# aquaMain.net
KiCad netlist of a schematic drawn in EAGLE
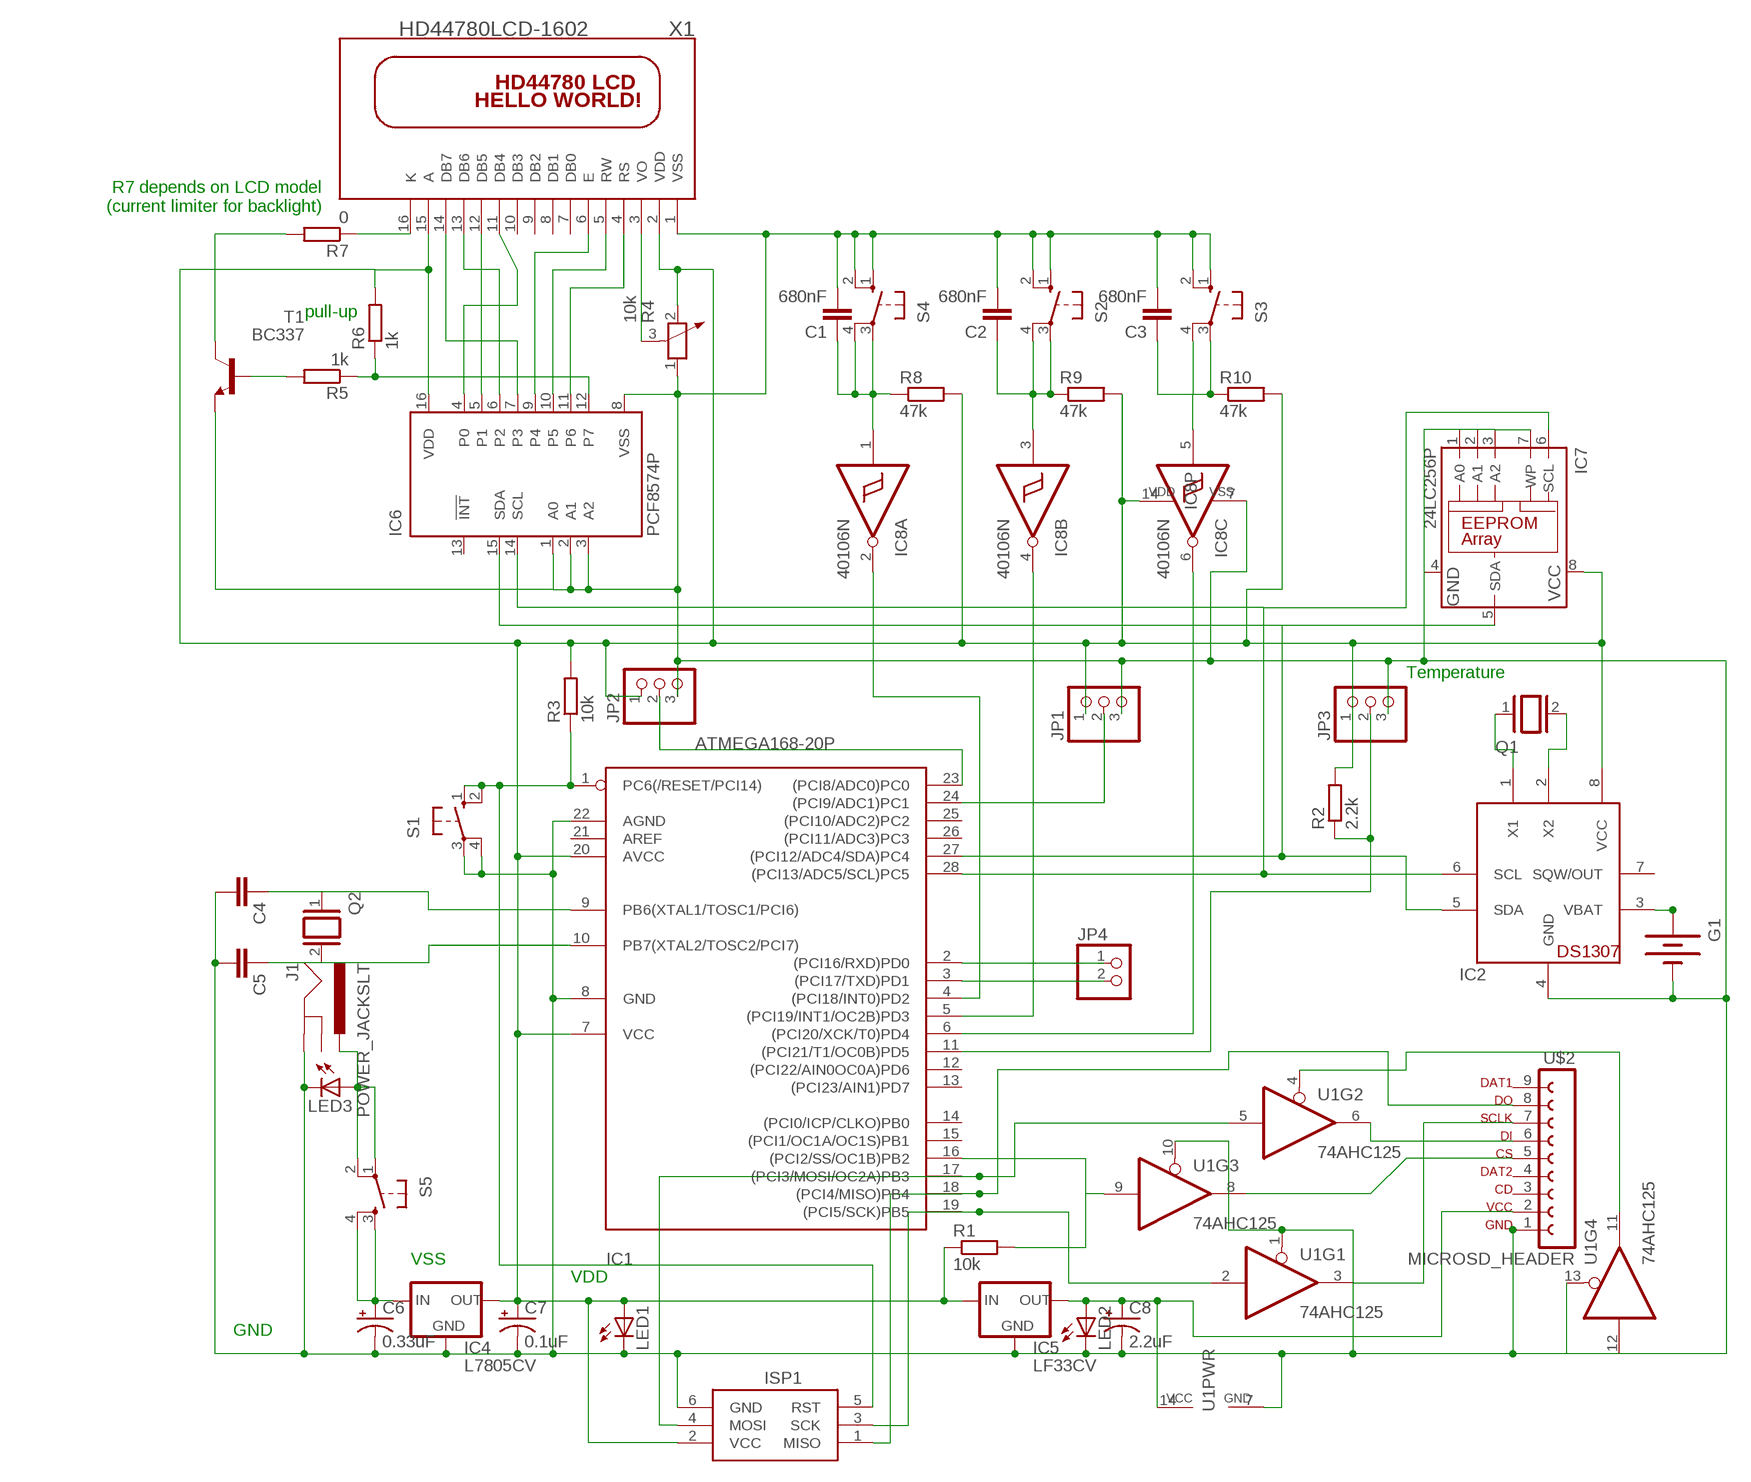
[diagram p0: schematic, sheet 1]

(export (version "E")
  (design (tool "Eeschema 10.0.6"))
  (components
    (comp (ref "C1")
      (value "680nF")
      (footprint "eagle-import:C050-050X075")
      (libsource (lib "eagle-import") (part "C-EU050-050X075"))
    )
    (comp (ref "C2")
      (value "680nF")
      (footprint "eagle-import:C050-050X075")
      (libsource (lib "eagle-import") (part "C-EU050-050X075"))
    )
    (comp (ref "C3")
      (value "680nF")
      (footprint "eagle-import:C050-050X075")
      (libsource (lib "eagle-import") (part "C-EU050-050X075"))
    )
    (comp (ref "C4")
      (value "C-EU025-024X044")
      (footprint "eagle-import:C025-024X044")
      (libsource (lib "eagle-import") (part "C-EU025-024X044"))
    )
    (comp (ref "C5")
      (value "C-EU025-024X044")
      (footprint "eagle-import:C025-024X044")
      (libsource (lib "eagle-import") (part "C-EU025-024X044"))
    )
    (comp (ref "C6")
      (value "0.33uF")
      (footprint "eagle-import:E5-6")
      (libsource (lib "eagle-import") (part "CPOL-USE5-6"))
    )
    (comp (ref "C7")
      (value "0.1uF")
      (footprint "eagle-import:E5-6")
      (libsource (lib "eagle-import") (part "CPOL-USE5-6"))
    )
    (comp (ref "C8")
      (value "2.2uF")
      (footprint "eagle-import:E5-6")
      (libsource (lib "eagle-import") (part "CPOL-USE5-6"))
    )
    (comp (ref "G1")
      (value "BATTERY20PTH")
      (footprint "eagle-import:BATTCOM_20MM_PTH")
      (libsource (lib "eagle-import") (part "BATTERY20PTH"))
    )
    (comp (ref "IC1")
      (value "ATMEGA168-20P")
      (footprint "eagle-import:DIL28-3")
      (libsource (lib "eagle-import") (part "ATMEGA168P-20"))
    )
    (comp (ref "IC2")
      (value "DS1307")
      (footprint "eagle-import:DIL08")
      (libsource (lib "eagle-import") (part "DS1307"))
    )
    (comp (ref "IC4")
      (value "L7805CV")
      (footprint "eagle-import:TO220")
      (libsource (lib "eagle-import") (part "L7805CV"))
    )
    (comp (ref "IC5")
      (value "LF33CV")
      (footprint "eagle-import:TO220")
      (libsource (lib "eagle-import") (part "LF33CV"))
    )
    (comp (ref "IC6")
      (value "PCF8574P")
      (footprint "eagle-import:DIL16")
      (fields (field (name "MPN") "PCF8574PN"))
      (libsource (lib "eagle-import") (part "PCF8574P"))
    )
    (comp (ref "IC7")
      (value "24LC256P")
      (footprint "eagle-import:DIL8")
      (fields (field (name "MF") "MICROCHIP") (field (name "MPN") "24LC256-E/P"))
      (libsource (lib "eagle-import") (part "24PLC256"))
    )
    (comp (ref "IC8")
      (value "40106N")
      (footprint "eagle-import:DIL14")
      (libsource (lib "eagle-import") (part "40106N"))
    )
    (comp (ref "ISP1")
      (value "AVRISP-6")
      (footprint "eagle-import:AVRISP")
      (libsource (lib "eagle-import") (part "AVRISP-6"))
    )
    (comp (ref "J1")
      (value "POWER_JACKSLT")
      (footprint "eagle-import:POWER_JACK_SLOT")
      (libsource (lib "eagle-import") (part "POWER_JACKSLT"))
    )
    (comp (ref "JP1")
      (value "PINHD-1X3")
      (footprint "eagle-import:1X03")
      (libsource (lib "eagle-import") (part "PINHD-1X3"))
    )
    (comp (ref "JP2")
      (value "PINHD-1X3")
      (footprint "eagle-import:1X03")
      (libsource (lib "eagle-import") (part "PINHD-1X3"))
    )
    (comp (ref "JP3")
      (value "PINHD-1X3")
      (footprint "eagle-import:1X03")
      (libsource (lib "eagle-import") (part "PINHD-1X3"))
    )
    (comp (ref "JP4")
      (value "PINHD-1X2")
      (footprint "eagle-import:1X02")
      (libsource (lib "eagle-import") (part "PINHD-1X2"))
    )
    (comp (ref "LED1")
      (value "LED3MM")
      (footprint "eagle-import:LED3MM")
      (libsource (lib "eagle-import") (part "LED3MM"))
    )
    (comp (ref "LED2")
      (value "LED3MM")
      (footprint "eagle-import:LED3MM")
      (libsource (lib "eagle-import") (part "LED3MM"))
    )
    (comp (ref "LED3")
      (value "LED3MM")
      (footprint "eagle-import:LED3MM")
      (libsource (lib "eagle-import") (part "LED3MM"))
    )
    (comp (ref "Q1")
      (value "XTAL/S")
      (footprint "eagle-import:QS")
      (libsource (lib "eagle-import") (part "XTAL/S"))
    )
    (comp (ref "Q2")
      (value "XTAL/S")
      (footprint "eagle-import:QS")
      (libsource (lib "eagle-import") (part "XTAL/S"))
    )
    (comp (ref "R1")
      (value "10k")
      (footprint "eagle-import:0204_7")
      (libsource (lib "eagle-import") (part "R-EU_0204/7"))
    )
    (comp (ref "R2")
      (value "2.2k")
      (footprint "eagle-import:0204_7")
      (libsource (lib "eagle-import") (part "R-EU_0204/7"))
    )
    (comp (ref "R3")
      (value "10k")
      (footprint "eagle-import:0204_7")
      (libsource (lib "eagle-import") (part "R-EU_0204/7"))
    )
    (comp (ref "R4")
      (value "10k")
      (footprint "eagle-import:PT-10")
      (libsource (lib "eagle-import") (part "POTENTIOMETER_PT-10"))
    )
    (comp (ref "R5")
      (value "1k")
      (footprint "eagle-import:0204_5")
      (libsource (lib "eagle-import") (part "R-EU_0204/5"))
    )
    (comp (ref "R6")
      (value "1k")
      (footprint "eagle-import:0204_5")
      (libsource (lib "eagle-import") (part "R-EU_0204/5"))
    )
    (comp (ref "R7")
      (value "0")
      (footprint "eagle-import:0204_5")
      (libsource (lib "eagle-import") (part "R-EU_0204/5"))
    )
    (comp (ref "R8")
      (value "47k")
      (footprint "eagle-import:0204_5")
      (libsource (lib "eagle-import") (part "R-EU_0204/5"))
    )
    (comp (ref "R9")
      (value "47k")
      (footprint "eagle-import:0204_5")
      (libsource (lib "eagle-import") (part "R-EU_0204/5"))
    )
    (comp (ref "R10")
      (value "47k")
      (footprint "eagle-import:0204_5")
      (libsource (lib "eagle-import") (part "R-EU_0204/5"))
    )
    (comp (ref "S1")
      (value "40-XX-ROUND")
      (footprint "eagle-import:B3F-40XX-ROUND")
      (libsource (lib "eagle-import") (part "40-XX-ROUND"))
    )
    (comp (ref "S2")
      (value "40-XX-ROUND")
      (footprint "eagle-import:B3F-40XX-ROUND")
      (libsource (lib "eagle-import") (part "40-XX-ROUND"))
    )
    (comp (ref "S3")
      (value "40-XX-ROUND")
      (footprint "eagle-import:B3F-40XX-ROUND")
      (libsource (lib "eagle-import") (part "40-XX-ROUND"))
    )
    (comp (ref "S4")
      (value "40-XX-ROUND")
      (footprint "eagle-import:B3F-40XX-ROUND")
      (libsource (lib "eagle-import") (part "40-XX-ROUND"))
    )
    (comp (ref "S5")
      (value "TAC_SWITCHPTH")
      (footprint "eagle-import:TACTILE-PTH")
      (libsource (lib "eagle-import") (part "TAC_SWITCHPTH"))
    )
    (comp (ref "T1")
      (value "BC337")
      (footprint "eagle-import:TO92")
      (libsource (lib "eagle-import") (part "BC337"))
    )
    (comp (ref "U$2")
      (value "MICROSD_HEADER")
      (footprint "eagle-import:9PINH")
      (libsource (lib "eagle-import") (part "MICROSD_HEADER"))
    )
    (comp (ref "U1")
      (value "74AHC125")
      (footprint "eagle-import:DIP14")
      (libsource (lib "eagle-import") (part "74AHC125"))
    )
    (comp (ref "X1")
      (value "HD44780LCD-1602")
      (footprint "eagle-import:LCD1602")
      (libsource (lib "eagle-import") (part "HD44780LCD-1602"))
    )
  )
  (nets
    (net (code "1") (name "Net-(G1-+)") (class "Default")
      (node (ref "G1") (pin "1") (pinfunction "+_1") (pintype "power_in"))
      (node (ref "IC2") (pin "3") (pinfunction "VBAT_3") (pintype "power_in"))
    )
    (net (code "2") (name "Net-(G1--)") (class "Default")
      (node (ref "C1") (pin "2") (pinfunction "2_2") (pintype "passive"))
      (node (ref "C2") (pin "2") (pinfunction "2_2") (pintype "passive"))
      (node (ref "C3") (pin "2") (pinfunction "2_2") (pintype "passive"))
      (node (ref "C4") (pin "2") (pinfunction "2_2") (pintype "passive"))
      (node (ref "C5") (pin "2") (pinfunction "2_2") (pintype "passive"))
      (node (ref "C6") (pin "-") (pinfunction "-_-") (pintype "passive"))
      (node (ref "C7") (pin "-") (pinfunction "-_-") (pintype "passive"))
      (node (ref "C8") (pin "-") (pinfunction "-_-") (pintype "passive"))
      (node (ref "G1") (pin "2") (pinfunction "-_2") (pintype "power_in"))
      (node (ref "IC1") (pin "22") (pinfunction "AGND_22") (pintype "bidirectional"))
      (node (ref "IC1") (pin "8") (pinfunction "GND_8") (pintype "bidirectional"))
      (node (ref "IC2") (pin "4") (pinfunction "GND_4") (pintype "power_in"))
      (node (ref "IC4") (pin "GND") (pinfunction "GND_GND") (pintype "input"))
      (node (ref "IC5") (pin "GND") (pinfunction "GND_GND") (pintype "input"))
      (node (ref "IC6") (pin "1") (pinfunction "A0_1") (pintype "input"))
      (node (ref "IC6") (pin "2") (pinfunction "A1_2") (pintype "input"))
      (node (ref "IC6") (pin "3") (pinfunction "A2_3") (pintype "input"))
      (node (ref "IC6") (pin "8") (pinfunction "VSS_8") (pintype "power_in"))
      (node (ref "IC7") (pin "1") (pinfunction "A0_1") (pintype "input"))
      (node (ref "IC7") (pin "2") (pinfunction "A1_2") (pintype "input"))
      (node (ref "IC7") (pin "3") (pinfunction "A2_3") (pintype "input"))
      (node (ref "IC7") (pin "4") (pinfunction "GND_4") (pintype "power_in"))
      (node (ref "IC7") (pin "7") (pinfunction "WP_7") (pintype "input"))
      (node (ref "IC8") (pin "7") (pinfunction "VSS_7") (pintype "power_in"))
      (node (ref "ISP1") (pin "6") (pinfunction "GND_6") (pintype "power_in"))
      (node (ref "J1") (pin "GND@2") (pinfunction "GND_GND@2") (pintype "bidirectional"))
      (node (ref "JP1") (pin "3") (pinfunction "3_3") (pintype "passive"))
      (node (ref "JP2") (pin "3") (pinfunction "3_3") (pintype "passive"))
      (node (ref "JP3") (pin "3") (pinfunction "3_3") (pintype "passive"))
      (node (ref "LED1") (pin "K") (pinfunction "C_K") (pintype "passive"))
      (node (ref "LED2") (pin "K") (pinfunction "C_K") (pintype "passive"))
      (node (ref "LED3") (pin "K") (pinfunction "C_K") (pintype "passive"))
      (node (ref "R4") (pin "1") (pinfunction "1_1") (pintype "passive"))
      (node (ref "S1") (pin "3") (pinfunction "P_3") (pintype "passive"))
      (node (ref "S1") (pin "4") (pinfunction "P1_4") (pintype "passive"))
      (node (ref "S2") (pin "1") (pinfunction "S_1") (pintype "passive"))
      (node (ref "S2") (pin "2") (pinfunction "S1_2") (pintype "passive"))
      (node (ref "S3") (pin "1") (pinfunction "S_1") (pintype "passive"))
      (node (ref "S3") (pin "2") (pinfunction "S1_2") (pintype "passive"))
      (node (ref "S4") (pin "1") (pinfunction "S_1") (pintype "passive"))
      (node (ref "S4") (pin "2") (pinfunction "S1_2") (pintype "passive"))
      (node (ref "T1") (pin "1") (pinfunction "E_1") (pintype "passive"))
      (node (ref "U$2") (pin "1") (pinfunction "1_1") (pintype "passive"))
      (node (ref "U1") (pin "1") (pinfunction "OE_1") (pintype "input"))
      (node (ref "U1") (pin "10") (pinfunction "OE_10") (pintype "input"))
      (node (ref "U1") (pin "12") (pinfunction "I_12") (pintype "input"))
      (node (ref "U1") (pin "13") (pinfunction "OE_13") (pintype "input"))
      (node (ref "U1") (pin "7") (pinfunction "GND_7") (pintype "power_in"))
      (node (ref "X1") (pin "1") (pinfunction "VSS_1") (pintype "power_in"))
    )
    (net (code "3") (name "Net-(IC1-(PCI2{slash}SS{slash}OC1B)PB2)") (class "Default")
      (node (ref "IC1") (pin "16") (pinfunction "(PCI2/SS/OC1B)PB2_16") (pintype "bidirectional"))
      (node (ref "R1") (pin "2") (pinfunction "2_2") (pintype "passive"))
      (node (ref "U1") (pin "9") (pinfunction "I_9") (pintype "input"))
    )
    (net (code "4") (name "Net-(IC1-(PCI3{slash}MOSI{slash}OC2A)PB3)") (class "Default")
      (node (ref "IC1") (pin "17") (pinfunction "(PCI3/MOSI/OC2A)PB3_17") (pintype "bidirectional"))
      (node (ref "ISP1") (pin "4") (pinfunction "MOSI_4") (pintype "output"))
      (node (ref "U1") (pin "5") (pinfunction "I_5") (pintype "input"))
    )
    (net (code "5") (name "Net-(IC1-(PCI4{slash}MISO)PB4)") (class "Default")
      (node (ref "IC1") (pin "18") (pinfunction "(PCI4/MISO)PB4_18") (pintype "bidirectional"))
      (node (ref "ISP1") (pin "1") (pinfunction "MISO_1") (pintype "input"))
      (node (ref "U$2") (pin "8") (pinfunction "8_8") (pintype "passive"))
    )
    (net (code "6") (name "Net-(IC1-(PCI5{slash}SCK)PB5)") (class "Default")
      (node (ref "IC1") (pin "19") (pinfunction "(PCI5/SCK)PB5_19") (pintype "bidirectional"))
      (node (ref "ISP1") (pin "3") (pinfunction "SCK_3") (pintype "output"))
      (node (ref "U1") (pin "2") (pinfunction "I_2") (pintype "input"))
    )
    (net (code "7") (name "Net-(IC1-(PCI8{slash}ADC0)PC0)") (class "Default")
      (node (ref "IC1") (pin "23") (pinfunction "(PCI8/ADC0)PC0_23") (pintype "bidirectional"))
      (node (ref "JP2") (pin "2") (pinfunction "2_2") (pintype "passive"))
    )
    (net (code "8") (name "Net-(IC1-(PCI9{slash}ADC1)PC1)") (class "Default")
      (node (ref "IC1") (pin "24") (pinfunction "(PCI9/ADC1)PC1_24") (pintype "bidirectional"))
      (node (ref "JP1") (pin "2") (pinfunction "2_2") (pintype "passive"))
    )
    (net (code "9") (name "Net-(IC1-(PCI12{slash}ADC4{slash}SDA)PC4)") (class "Default")
      (node (ref "IC1") (pin "27") (pinfunction "(PCI12/ADC4/SDA)PC4_27") (pintype "bidirectional"))
      (node (ref "IC2") (pin "5") (pinfunction "SDA_5") (pintype "bidirectional"))
      (node (ref "IC6") (pin "15") (pinfunction "SDA_15") (pintype "bidirectional"))
      (node (ref "IC7") (pin "5") (pinfunction "SDA_5") (pintype "bidirectional"))
    )
    (net (code "10") (name "Net-(IC1-(PCI13{slash}ADC5{slash}SCL)PC5)") (class "Default")
      (node (ref "IC1") (pin "28") (pinfunction "(PCI13/ADC5/SCL)PC5_28") (pintype "bidirectional"))
      (node (ref "IC2") (pin "6") (pinfunction "SCL_6") (pintype "bidirectional"))
      (node (ref "IC6") (pin "14") (pinfunction "SCL_14") (pintype "input"))
      (node (ref "IC7") (pin "6") (pinfunction "SCL_6") (pintype "input"))
    )
    (net (code "11") (name "Net-(IC1-(PCI16{slash}RXD)PD0)") (class "Default")
      (node (ref "IC1") (pin "2") (pinfunction "(PCI16/RXD)PD0_2") (pintype "bidirectional"))
      (node (ref "JP4") (pin "1") (pinfunction "1_1") (pintype "passive"))
    )
    (net (code "12") (name "Net-(IC1-(PCI17{slash}TXD)PD1)") (class "Default")
      (node (ref "IC1") (pin "3") (pinfunction "(PCI17/TXD)PD1_3") (pintype "bidirectional"))
      (node (ref "JP4") (pin "2") (pinfunction "2_2") (pintype "passive"))
    )
    (net (code "13") (name "Net-(IC1-(PCI18{slash}INT0)PD2)") (class "Default")
      (node (ref "IC1") (pin "4") (pinfunction "(PCI18/INT0)PD2_4") (pintype "bidirectional"))
      (node (ref "IC8") (pin "2") (pinfunction "O_2") (pintype "output"))
    )
    (net (code "14") (name "Net-(IC1-(PCI19{slash}INT1{slash}OC2B)PD3)") (class "Default")
      (node (ref "IC1") (pin "5") (pinfunction "(PCI19/INT1/OC2B)PD3_5") (pintype "bidirectional"))
      (node (ref "IC8") (pin "4") (pinfunction "O_4") (pintype "output"))
    )
    (net (code "15") (name "Net-(IC1-(PCI20{slash}XCK{slash}T0)PD4)") (class "Default")
      (node (ref "IC1") (pin "6") (pinfunction "(PCI20/XCK/T0)PD4_6") (pintype "bidirectional"))
      (node (ref "IC8") (pin "6") (pinfunction "O_6") (pintype "output"))
    )
    (net (code "16") (name "Net-(IC1-(PCI21{slash}T1{slash}OC0B)PD5)") (class "Default")
      (node (ref "IC1") (pin "11") (pinfunction "(PCI21/T1/OC0B)PD5_11") (pintype "bidirectional"))
      (node (ref "JP3") (pin "2") (pinfunction "2_2") (pintype "passive"))
      (node (ref "R2") (pin "1") (pinfunction "1_1") (pintype "passive"))
    )
    (net (code "17") (name "Net-(IC1-AVCC)") (class "Default")
      (node (ref "C7") (pin "+") (pinfunction "+_+") (pintype "passive"))
      (node (ref "IC1") (pin "20") (pinfunction "AVCC_20") (pintype "bidirectional"))
      (node (ref "IC1") (pin "7") (pinfunction "VCC_7") (pintype "bidirectional"))
      (node (ref "IC2") (pin "8") (pinfunction "VCC_8") (pintype "power_in"))
      (node (ref "IC4") (pin "VOUT") (pinfunction "OUT_VOUT") (pintype "output"))
      (node (ref "IC5") (pin "VIN") (pinfunction "IN_VIN") (pintype "input"))
      (node (ref "IC6") (pin "16") (pinfunction "VDD_16") (pintype "power_in"))
      (node (ref "IC7") (pin "8") (pinfunction "VCC_8") (pintype "power_in"))
      (node (ref "IC8") (pin "14") (pinfunction "VDD_14") (pintype "power_in"))
      (node (ref "ISP1") (pin "2") (pinfunction "VCC_2") (pintype "power_in"))
      (node (ref "JP1") (pin "1") (pinfunction "1_1") (pintype "passive"))
      (node (ref "JP2") (pin "1") (pinfunction "1_1") (pintype "passive"))
      (node (ref "JP3") (pin "1") (pinfunction "1_1") (pintype "passive"))
      (node (ref "LED1") (pin "A") (pinfunction "A_A") (pintype "passive"))
      (node (ref "R1") (pin "1") (pinfunction "1_1") (pintype "passive"))
      (node (ref "R10") (pin "2") (pinfunction "2_2") (pintype "passive"))
      (node (ref "R2") (pin "2") (pinfunction "2_2") (pintype "passive"))
      (node (ref "R3") (pin "2") (pinfunction "2_2") (pintype "passive"))
      (node (ref "R4") (pin "2") (pinfunction "2_2") (pintype "passive"))
      (node (ref "R6") (pin "2") (pinfunction "2_2") (pintype "passive"))
      (node (ref "R8") (pin "2") (pinfunction "2_2") (pintype "passive"))
      (node (ref "R9") (pin "2") (pinfunction "2_2") (pintype "passive"))
      (node (ref "X1") (pin "15") (pinfunction "A_15") (pintype "input"))
      (node (ref "X1") (pin "2") (pinfunction "VDD_2") (pintype "power_in"))
    )
    (net (code "18") (name "Net-(IC1-PB6(XTAL1{slash}TOSC1{slash}PCI6))") (class "Default")
      (node (ref "C4") (pin "1") (pinfunction "1_1") (pintype "passive"))
      (node (ref "IC1") (pin "9") (pinfunction "PB6(XTAL1/TOSC1/PCI6)_9") (pintype "bidirectional"))
      (node (ref "Q2") (pin "1") (pinfunction "1_1") (pintype "passive"))
    )
    (net (code "19") (name "Net-(IC1-PB7(XTAL2{slash}TOSC2{slash}PCI7))") (class "Default")
      (node (ref "C5") (pin "1") (pinfunction "1_1") (pintype "passive"))
      (node (ref "IC1") (pin "10") (pinfunction "PB7(XTAL2/TOSC2/PCI7)_10") (pintype "bidirectional"))
      (node (ref "Q2") (pin "2") (pinfunction "2_2") (pintype "passive"))
    )
    (net (code "20") (name "Net-(IC1-PC6({slash}RESET{slash}PCI14))") (class "Default")
      (node (ref "IC1") (pin "1") (pinfunction "PC6(/RESET/PCI14)_1") (pintype "bidirectional"))
      (node (ref "ISP1") (pin "5") (pinfunction "RST_5") (pintype "output"))
      (node (ref "R3") (pin "1") (pinfunction "1_1") (pintype "passive"))
      (node (ref "S1") (pin "1") (pinfunction "S_1") (pintype "passive"))
      (node (ref "S1") (pin "2") (pinfunction "S1_2") (pintype "passive"))
    )
    (net (code "21") (name "Net-(IC2-X1)") (class "Default")
      (node (ref "IC2") (pin "1") (pinfunction "X1_1") (pintype "passive"))
      (node (ref "Q1") (pin "1") (pinfunction "1_1") (pintype "passive"))
    )
    (net (code "22") (name "Net-(IC2-X2)") (class "Default")
      (node (ref "IC2") (pin "2") (pinfunction "X2_2") (pintype "passive"))
      (node (ref "Q1") (pin "2") (pinfunction "2_2") (pintype "passive"))
    )
    (net (code "23") (name "Net-(IC4-IN)") (class "Default")
      (node (ref "C6") (pin "+") (pinfunction "+_+") (pintype "passive"))
      (node (ref "IC4") (pin "VIN") (pinfunction "IN_VIN") (pintype "input"))
      (node (ref "S5") (pin "3") (pinfunction "3_3") (pintype "passive"))
      (node (ref "S5") (pin "4") (pinfunction "4_4") (pintype "passive"))
    )
    (net (code "24") (name "Net-(IC5-OUT)") (class "Default")
      (node (ref "C8") (pin "+") (pinfunction "+_+") (pintype "passive"))
      (node (ref "IC5") (pin "VOUT") (pinfunction "OUT_VOUT") (pintype "output"))
      (node (ref "LED2") (pin "A") (pinfunction "A_A") (pintype "passive"))
      (node (ref "U$2") (pin "2") (pinfunction "2_2") (pintype "passive"))
      (node (ref "U1") (pin "14") (pinfunction "VCC_14") (pintype "power_in"))
    )
    (net (code "25") (name "Net-(IC6-P0)") (class "Default")
      (node (ref "IC6") (pin "4") (pinfunction "P0_4") (pintype "bidirectional"))
      (node (ref "X1") (pin "11") (pinfunction "DB4_11") (pintype "bidirectional"))
    )
    (net (code "26") (name "Net-(IC6-P1)") (class "Default")
      (node (ref "IC6") (pin "5") (pinfunction "P1_5") (pintype "bidirectional"))
      (node (ref "X1") (pin "12") (pinfunction "DB5_12") (pintype "bidirectional"))
    )
    (net (code "27") (name "Net-(IC6-P2)") (class "Default")
      (node (ref "IC6") (pin "6") (pinfunction "P2_6") (pintype "bidirectional"))
      (node (ref "X1") (pin "13") (pinfunction "DB6_13") (pintype "bidirectional"))
    )
    (net (code "28") (name "Net-(IC6-P3)") (class "Default")
      (node (ref "IC6") (pin "7") (pinfunction "P3_7") (pintype "bidirectional"))
      (node (ref "X1") (pin "14") (pinfunction "DB7_14") (pintype "bidirectional"))
    )
    (net (code "29") (name "Net-(IC6-P4)") (class "Default")
      (node (ref "IC6") (pin "9") (pinfunction "P4_9") (pintype "bidirectional"))
      (node (ref "X1") (pin "6") (pinfunction "E_6") (pintype "input"))
    )
    (net (code "30") (name "Net-(IC6-P5)") (class "Default")
      (node (ref "IC6") (pin "10") (pinfunction "P5_10") (pintype "bidirectional"))
      (node (ref "X1") (pin "5") (pinfunction "RW_5") (pintype "input"))
    )
    (net (code "31") (name "Net-(IC6-P6)") (class "Default")
      (node (ref "IC6") (pin "11") (pinfunction "P6_11") (pintype "bidirectional"))
      (node (ref "X1") (pin "4") (pinfunction "RS_4") (pintype "input"))
    )
    (net (code "32") (name "Net-(IC6-P7)") (class "Default")
      (node (ref "IC6") (pin "12") (pinfunction "P7_12") (pintype "bidirectional"))
      (node (ref "R5") (pin "1") (pinfunction "1_1") (pintype "passive"))
      (node (ref "R6") (pin "1") (pinfunction "1_1") (pintype "passive"))
    )
    (net (code "33") (name "Net-(IC8A-I)") (class "Default")
      (node (ref "C1") (pin "1") (pinfunction "1_1") (pintype "passive"))
      (node (ref "IC8") (pin "1") (pinfunction "I_1") (pintype "input"))
      (node (ref "R8") (pin "1") (pinfunction "1_1") (pintype "passive"))
      (node (ref "S4") (pin "3") (pinfunction "P_3") (pintype "passive"))
      (node (ref "S4") (pin "4") (pinfunction "P1_4") (pintype "passive"))
    )
    (net (code "34") (name "Net-(IC8B-I)") (class "Default")
      (node (ref "C2") (pin "1") (pinfunction "1_1") (pintype "passive"))
      (node (ref "IC8") (pin "3") (pinfunction "I_3") (pintype "input"))
      (node (ref "R9") (pin "1") (pinfunction "1_1") (pintype "passive"))
      (node (ref "S2") (pin "3") (pinfunction "P_3") (pintype "passive"))
      (node (ref "S2") (pin "4") (pinfunction "P1_4") (pintype "passive"))
    )
    (net (code "35") (name "Net-(IC8C-I)") (class "Default")
      (node (ref "C3") (pin "1") (pinfunction "1_1") (pintype "passive"))
      (node (ref "IC8") (pin "5") (pinfunction "I_5") (pintype "input"))
      (node (ref "R10") (pin "1") (pinfunction "1_1") (pintype "passive"))
      (node (ref "S3") (pin "3") (pinfunction "P_3") (pintype "passive"))
      (node (ref "S3") (pin "4") (pinfunction "P1_4") (pintype "passive"))
    )
    (net (code "36") (name "Net-(J1-PadPWR)") (class "Default")
      (node (ref "J1") (pin "PWR") (pinfunction "PWR_PWR") (pintype "bidirectional"))
      (node (ref "LED3") (pin "A") (pinfunction "A_A") (pintype "passive"))
      (node (ref "S5") (pin "1") (pinfunction "1_1") (pintype "passive"))
      (node (ref "S5") (pin "2") (pinfunction "2_2") (pintype "passive"))
    )
    (net (code "37") (name "Net-(T1-B)") (class "Default")
      (node (ref "R5") (pin "2") (pinfunction "2_2") (pintype "passive"))
      (node (ref "T1") (pin "2") (pinfunction "B_2") (pintype "passive"))
    )
    (net (code "38") (name "Net-(T1-C)") (class "Default")
      (node (ref "R7") (pin "2") (pinfunction "2_2") (pintype "passive"))
      (node (ref "T1") (pin "3") (pinfunction "C_3") (pintype "passive"))
    )
    (net (code "39") (name "Net-(U1A-O)") (class "Default")
      (node (ref "U$2") (pin "7") (pinfunction "7_7") (pintype "passive"))
      (node (ref "U1") (pin "3") (pinfunction "O_3") (pintype "tri_state"))
    )
    (net (code "40") (name "Net-(U1B-O)") (class "Default")
      (node (ref "U$2") (pin "6") (pinfunction "6_6") (pintype "passive"))
      (node (ref "U1") (pin "6") (pinfunction "O_6") (pintype "tri_state"))
    )
    (net (code "41") (name "Net-(U1B-OE)") (class "Default")
      (node (ref "U1") (pin "11") (pinfunction "O_11") (pintype "tri_state"))
      (node (ref "U1") (pin "4") (pinfunction "OE_4") (pintype "input"))
    )
    (net (code "42") (name "Net-(U1C-O)") (class "Default")
      (node (ref "U$2") (pin "5") (pinfunction "5_5") (pintype "passive"))
      (node (ref "U1") (pin "8") (pinfunction "O_8") (pintype "tri_state"))
    )
    (net (code "43") (name "Net-(X1-K)") (class "Default")
      (node (ref "R7") (pin "1") (pinfunction "1_1") (pintype "passive"))
      (node (ref "X1") (pin "16") (pinfunction "K_16") (pintype "input"))
    )
    (net (code "44") (name "Net-(X1-VO)") (class "Default")
      (node (ref "R4") (pin "3") (pinfunction "3_3") (pintype "passive"))
      (node (ref "X1") (pin "3") (pinfunction "VO_3") (pintype "input"))
    )
    (net (code "45") (name "unconnected-(IC1-(PCI0{slash}ICP{slash}CLKO)PB0-Pad14)") (class "Default")
      (node (ref "IC1") (pin "14") (pinfunction "(PCI0/ICP/CLKO)PB0_14") (pintype "bidirectional"))
    )
    (net (code "46") (name "unconnected-(IC1-(PCI1{slash}OC1A{slash}OC1S)PB1-Pad15)") (class "Default")
      (node (ref "IC1") (pin "15") (pinfunction "(PCI1/OC1A/OC1S)PB1_15") (pintype "bidirectional"))
    )
    (net (code "47") (name "unconnected-(IC1-(PCI10{slash}ADC2)PC2-Pad25)") (class "Default")
      (node (ref "IC1") (pin "25") (pinfunction "(PCI10/ADC2)PC2_25") (pintype "bidirectional"))
    )
    (net (code "48") (name "unconnected-(IC1-(PCI11{slash}ADC3)PC3-Pad26)") (class "Default")
      (node (ref "IC1") (pin "26") (pinfunction "(PCI11/ADC3)PC3_26") (pintype "bidirectional"))
    )
    (net (code "49") (name "unconnected-(IC1-(PCI22{slash}AIN0OC0A)PD6-Pad12)") (class "Default")
      (node (ref "IC1") (pin "12") (pinfunction "(PCI22/AIN0OC0A)PD6_12") (pintype "bidirectional"))
    )
    (net (code "50") (name "unconnected-(IC1-(PCI23{slash}AIN1)PD7-Pad13)") (class "Default")
      (node (ref "IC1") (pin "13") (pinfunction "(PCI23/AIN1)PD7_13") (pintype "bidirectional"))
    )
    (net (code "51") (name "unconnected-(IC1-AREF-Pad21)") (class "Default")
      (node (ref "IC1") (pin "21") (pinfunction "AREF_21") (pintype "bidirectional"))
    )
    (net (code "52") (name "unconnected-(IC2-SQW{slash}OUT-Pad7)") (class "Default")
      (node (ref "IC2") (pin "7") (pinfunction "SQW/OUT_7") (pintype "bidirectional"))
    )
    (net (code "53") (name "unconnected-(IC6-~{INT}-Pad13)") (class "Default")
      (node (ref "IC6") (pin "13") (pinfunction "~{INT}_13") (pintype "output"))
    )
    (net (code "54") (name "unconnected-(J1-GNDBREAK-PadGND@1)") (class "Default")
      (node (ref "J1") (pin "GND@1") (pinfunction "GNDBREAK_GND@1") (pintype "bidirectional"))
    )
    (net (code "55") (name "unconnected-(U$2-Pad3)") (class "Default")
      (node (ref "U$2") (pin "3") (pinfunction "3_3") (pintype "passive"))
    )
    (net (code "56") (name "unconnected-(U$2-Pad4)") (class "Default")
      (node (ref "U$2") (pin "4") (pinfunction "4_4") (pintype "passive"))
    )
    (net (code "57") (name "unconnected-(U$2-Pad9)") (class "Default")
      (node (ref "U$2") (pin "9") (pinfunction "9_9") (pintype "passive"))
    )
    (net (code "58") (name "unconnected-(X1-DB0-Pad7)") (class "Default")
      (node (ref "X1") (pin "7") (pinfunction "DB0_7") (pintype "bidirectional"))
    )
    (net (code "59") (name "unconnected-(X1-DB1-Pad8)") (class "Default")
      (node (ref "X1") (pin "8") (pinfunction "DB1_8") (pintype "bidirectional"))
    )
    (net (code "60") (name "unconnected-(X1-DB2-Pad9)") (class "Default")
      (node (ref "X1") (pin "9") (pinfunction "DB2_9") (pintype "bidirectional"))
    )
    (net (code "61") (name "unconnected-(X1-DB3-Pad10)") (class "Default")
      (node (ref "X1") (pin "10") (pinfunction "DB3_10") (pintype "bidirectional"))
    )
  )
)
